# Driver.net
KiCad netlist of a schematic drawn in Altium Designer
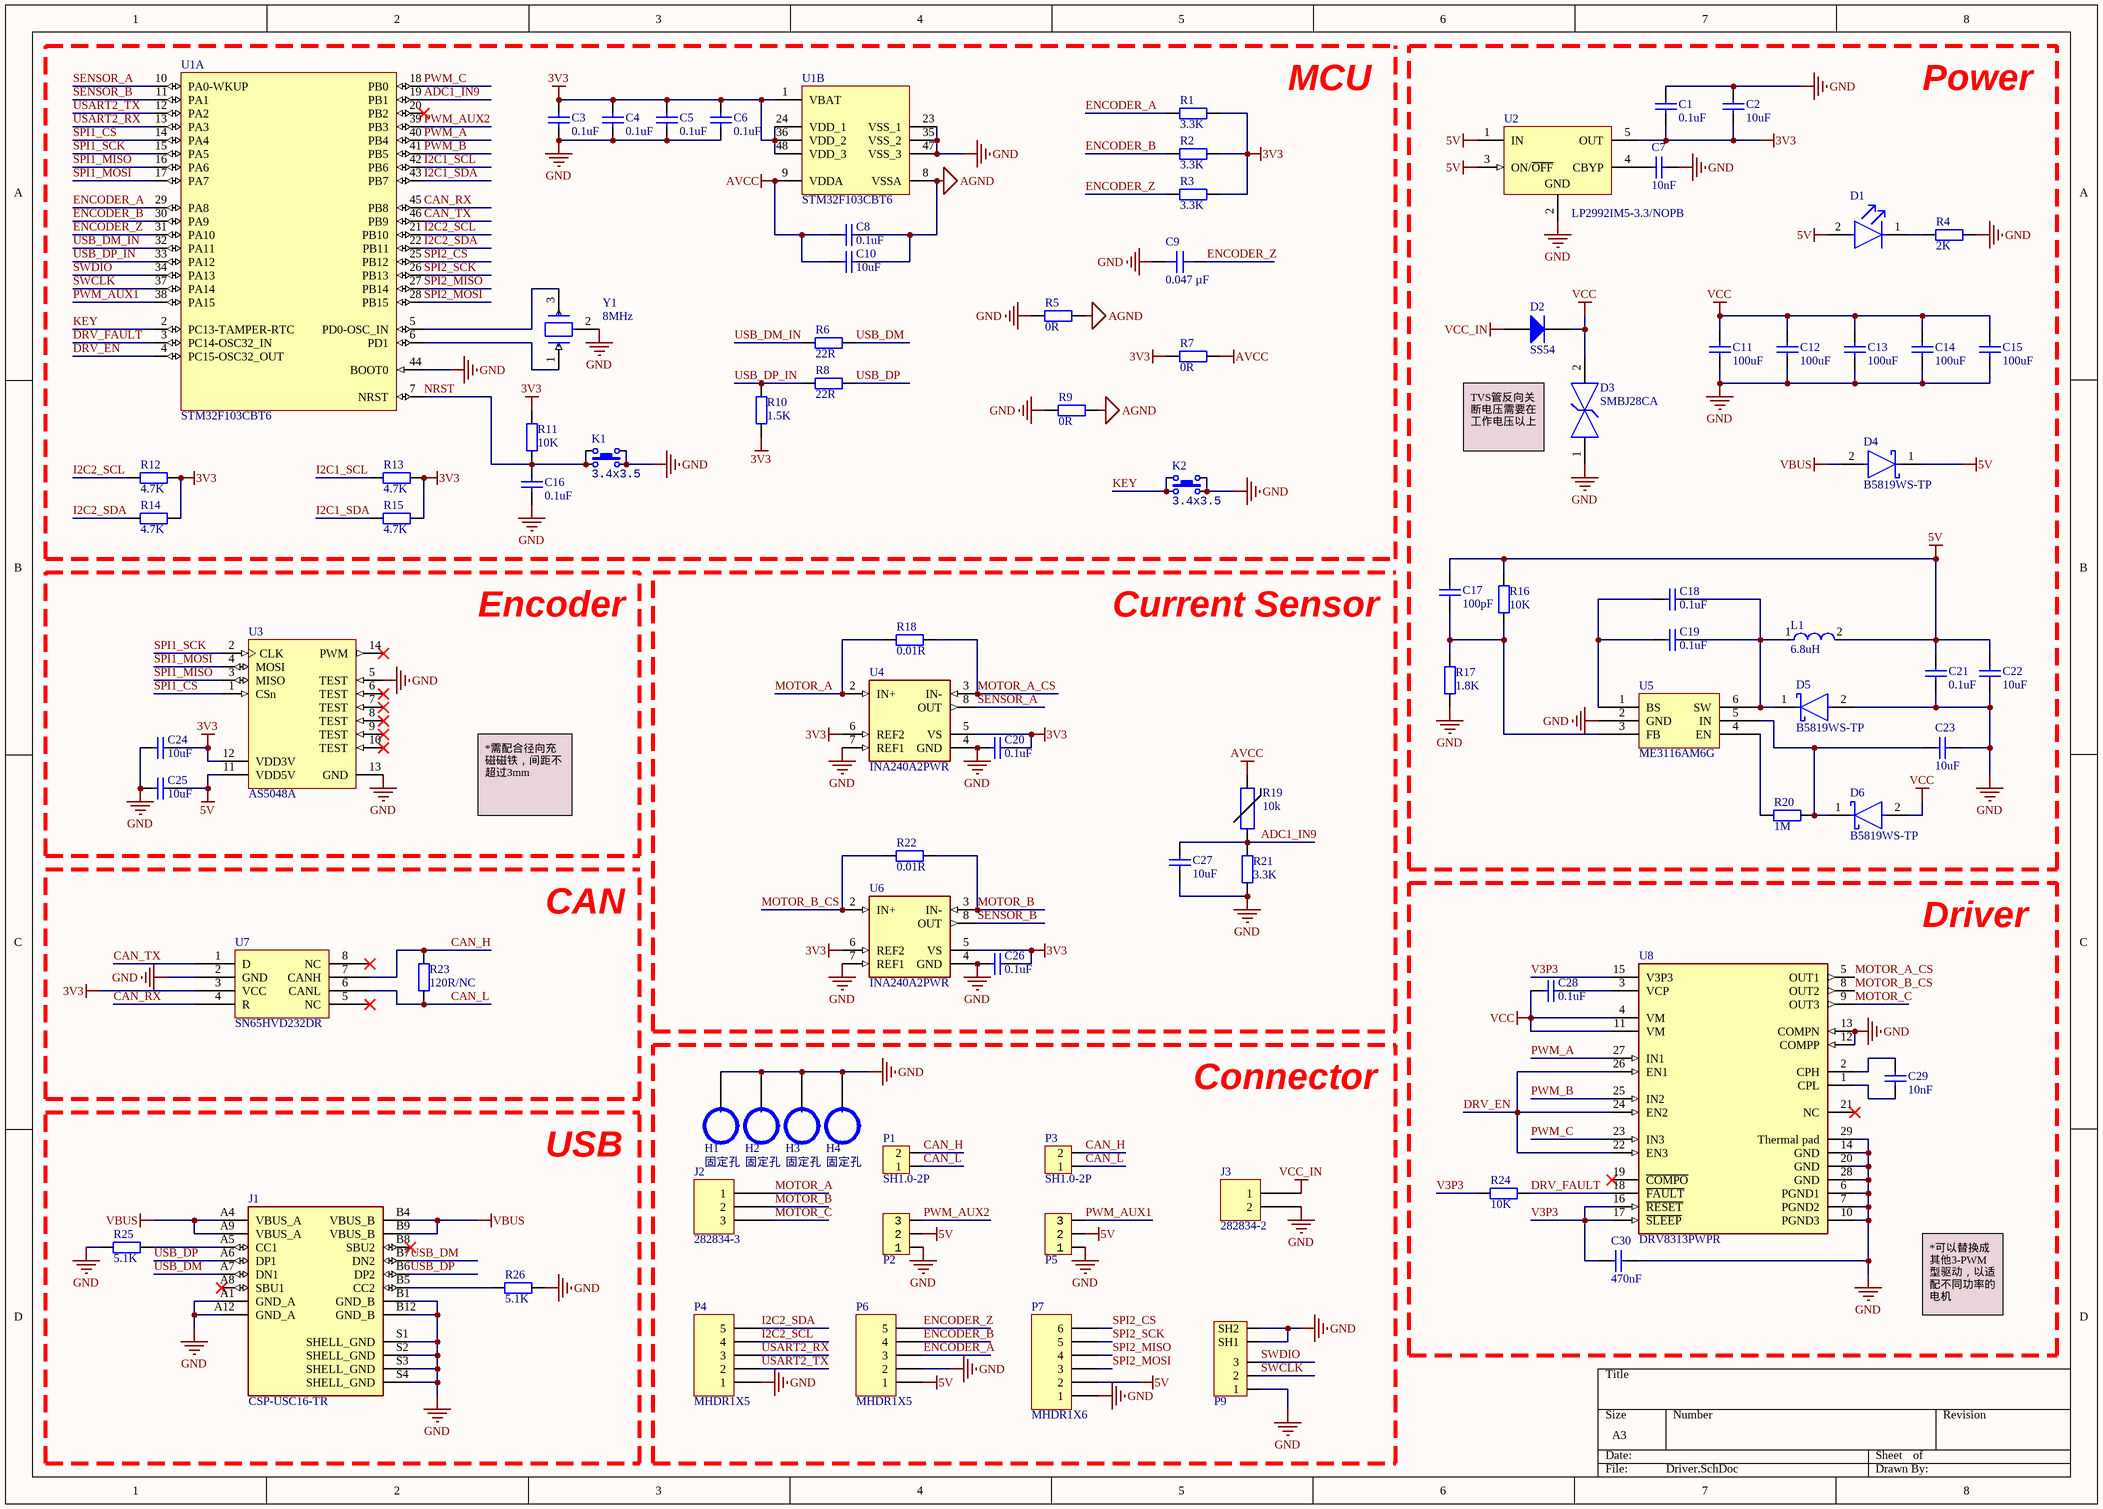
[diagram p0: Driver.SchDoc]

(export (version "E")
  (design (tool "Eeschema 10.0.6"))
  (components
    (comp (ref "C1")
      (value "0.1uF")
      (footprint "0402_C")
      (description "贴片电容")
      (libsource (lib "Miscellaneous Devices LC") (part "0402 100nF (104) 10% 16V"))
    )
    (comp (ref "C2")
      (value "10uF")
      (footprint "0402_C")
      (description "贴片电容")
      (libsource (lib "Miscellaneous Devices LC") (part "0402 100nF (104) 10% 16V"))
    )
    (comp (ref "C3")
      (value "0.1uF")
      (footprint "0402_C")
      (description "贴片电容")
      (libsource (lib "Miscellaneous Devices LC") (part "0402 100nF (104) 10% 16V"))
    )
    (comp (ref "C4")
      (value "0.1uF")
      (footprint "0402_C")
      (description "贴片电容")
      (libsource (lib "Miscellaneous Devices LC") (part "0402 100nF (104) 10% 16V"))
    )
    (comp (ref "C5")
      (value "0.1uF")
      (footprint "0402_C")
      (description "贴片电容")
      (libsource (lib "Miscellaneous Devices LC") (part "0402 100nF (104) 10% 16V"))
    )
    (comp (ref "C6")
      (value "0.1uF")
      (footprint "0402_C")
      (description "贴片电容")
      (libsource (lib "Miscellaneous Devices LC") (part "0402 100nF (104) 10% 16V"))
    )
    (comp (ref "C7")
      (value "10nF")
      (footprint "0402_C")
      (description "贴片电容")
      (libsource (lib "Miscellaneous Devices LC") (part "0402 100nF (104) 10% 16V"))
    )
    (comp (ref "C8")
      (value "0.1uF")
      (footprint "0402_C")
      (description "贴片电容")
      (libsource (lib "Miscellaneous Devices LC") (part "0402 100nF (104) 10% 16V"))
    )
    (comp (ref "C9")
      (value "0.047 µF")
      (footprint "CAP 0402_1005")
      (description "CAP CER 0402 47NF 25V X7R 10%")
      (fields (field (name "PART NUMBER") "C0402C473K3REC7867") (field (name "MANUFACTURER") "KEMET"))
      (libsource (lib "Celestial Altium Library - altium_library") (part "Capacitor"))
    )
    (comp (ref "C10")
      (value "10uF")
      (footprint "0402_C")
      (description "贴片电容")
      (libsource (lib "Miscellaneous Devices LC") (part "0402 100nF (104) 10% 16V"))
    )
    (comp (ref "C11")
      (value "100uF")
      (footprint "CAPC3216X190X55LL30T25")
      (description "Chip Capacitor, 100 uF, +/- 20%, 6.3 V, -55 to 85 degC, 1206 (3216 Metric), RoHS, Tape and Reel")
      (fields (field (name "TOLERANCE") "20%") (field (name "PARTNUMBER") "GRM31CR60J107ME39L"))
      (libsource (lib "Altium Content Vault") (part "CAP-NP-2"))
    )
    (comp (ref "C12")
      (value "100uF")
      (footprint "CAPC3216X190X55LL30T25")
      (description "Chip Capacitor, 100 uF, +/- 20%, 6.3 V, -55 to 85 degC, 1206 (3216 Metric), RoHS, Tape and Reel")
      (fields (field (name "TOLERANCE") "20%") (field (name "PARTNUMBER") "GRM31CR60J107ME39L"))
      (libsource (lib "Altium Content Vault") (part "CAP-NP-2"))
    )
    (comp (ref "C13")
      (value "100uF")
      (footprint "CAPC3216X190X55LL30T25")
      (description "Chip Capacitor, 100 uF, +/- 20%, 6.3 V, -55 to 85 degC, 1206 (3216 Metric), RoHS, Tape and Reel")
      (fields (field (name "TOLERANCE") "20%") (field (name "PARTNUMBER") "GRM31CR60J107ME39L"))
      (libsource (lib "Altium Content Vault") (part "CAP-NP-2"))
    )
    (comp (ref "C14")
      (value "100uF")
      (footprint "CAPC3216X190X55LL30T25")
      (description "Chip Capacitor, 100 uF, +/- 20%, 6.3 V, -55 to 85 degC, 1206 (3216 Metric), RoHS, Tape and Reel")
      (fields (field (name "TOLERANCE") "20%") (field (name "PARTNUMBER") "GRM31CR60J107ME39L"))
      (libsource (lib "Altium Content Vault") (part "CAP-NP-2"))
    )
    (comp (ref "C15")
      (value "100uF")
      (footprint "CAPC3216X190X55LL30T25")
      (description "Chip Capacitor, 100 uF, +/- 20%, 6.3 V, -55 to 85 degC, 1206 (3216 Metric), RoHS, Tape and Reel")
      (fields (field (name "TOLERANCE") "20%") (field (name "PARTNUMBER") "GRM31CR60J107ME39L"))
      (libsource (lib "Altium Content Vault") (part "CAP-NP-2"))
    )
    (comp (ref "C16")
      (value "0.1uF")
      (footprint "0402_C")
      (description "贴片电容")
      (libsource (lib "Miscellaneous Devices LC") (part "0402 100nF (104) 10% 16V"))
    )
    (comp (ref "C17")
      (value "100pF")
      (footprint "0402_C")
      (description "贴片电容")
      (libsource (lib "Miscellaneous Devices LC") (part "0402 100pF (101) 5% 50V"))
    )
    (comp (ref "C18")
      (value "0.1uF")
      (footprint "0402_C")
      (description "贴片电容")
      (libsource (lib "Miscellaneous Devices LC") (part "0402 100nF (104) 10% 16V"))
    )
    (comp (ref "C19")
      (value "0.1uF")
      (footprint "0402_C")
      (description "贴片电容")
      (libsource (lib "Miscellaneous Devices LC") (part "0402 100nF (104) 10% 16V"))
    )
    (comp (ref "C20")
      (value "0.1uF")
      (footprint "0402_C")
      (description "贴片电容")
      (libsource (lib "Miscellaneous Devices LC") (part "0402 100nF (104) 10% 16V"))
    )
    (comp (ref "C21")
      (value "0.1uF")
      (footprint "0402_C")
      (description "贴片电容")
      (libsource (lib "Miscellaneous Devices LC") (part "0402 100nF (104) 10% 16V"))
    )
    (comp (ref "C22")
      (value "10uF")
      (footprint "0402_C")
      (description "贴片电容")
      (libsource (lib "Miscellaneous Devices LC") (part "0402 100nF (104) 10% 16V"))
    )
    (comp (ref "C23")
      (value "10uF")
      (footprint "0402_C")
      (description "贴片电容")
      (libsource (lib "Miscellaneous Devices LC") (part "0402 100nF (104) 10% 16V"))
    )
    (comp (ref "C24")
      (value "10uF")
      (footprint "0402_C")
      (description "贴片电容")
      (libsource (lib "Miscellaneous Devices LC") (part "0402 100nF (104) 10% 16V"))
    )
    (comp (ref "C25")
      (value "10uF")
      (footprint "0402_C")
      (description "贴片电容")
      (libsource (lib "Miscellaneous Devices LC") (part "0402 100nF (104) 10% 16V"))
    )
    (comp (ref "C26")
      (value "0.1uF")
      (footprint "0402_C")
      (description "贴片电容")
      (libsource (lib "Miscellaneous Devices LC") (part "0402 100nF (104) 10% 16V"))
    )
    (comp (ref "C27")
      (value "10uF")
      (footprint "0402_C")
      (description "贴片电容")
      (libsource (lib "Miscellaneous Devices LC") (part "0402 100nF (104) 10% 16V"))
    )
    (comp (ref "C28")
      (value "0.1uF")
      (footprint "0402_C")
      (description "贴片电容")
      (libsource (lib "Miscellaneous Devices LC") (part "0402 100nF (104) 10% 16V"))
    )
    (comp (ref "C29")
      (value "10nF")
      (footprint "0402_C")
      (description "贴片电容")
      (libsource (lib "Miscellaneous Devices LC") (part "0402 10nF (103) 10% 50V"))
    )
    (comp (ref "C30")
      (value "470nF")
      (footprint "0402_C")
      (description "贴片电容")
      (libsource (lib "Miscellaneous Devices LC") (part "0402 470nF (474) 10% 10V"))
    )
    (comp (ref "D1")
      (value "~")
      (footprint "FP-APHHS1005CGCK-MFG")
      (description "LED GREEN CLEAR CHIP SMD")
      (libsource (lib "Altium Content Vault") (part "8706943c75ba83719d021d2fdc84c58"))
    )
    (comp (ref "D2")
      (value "SS54")
      (footprint "SMA(DO-214AC)_S1")
      (description "二极管")
      (libsource (lib "Miscellaneous Devices LC") (part "SMA(DO-214AC) SS54"))
    )
    (comp (ref "D3")
      (value "SMBJ28CA")
      (footprint "FP-SMBJ-CA-MFG")
      (description "TVS DIODE 28V 45.4V DO214AA")
      (fields
        (field (name "MANUFACTURER") "Littelfuse Inc")
        (field (name "OCTOPART") "https://octopart.com/smbj28ca-littelfuse-350757")
      )
      (libsource (lib "Altium Content Vault") (part "89c663e49c8877d2c9d183c2997548d"))
    )
    (comp (ref "D4")
      (value "B5819WS-TP")
      (footprint "FP-SOD-323-IPC_C")
      (description "DIODE SCHOTTKY 40V 1A SOD323")
      (libsource (lib "Altium Content Vault") (part "1d6ec82d83fb6aee721767c19dac4b9"))
    )
    (comp (ref "D5")
      (value "B5819WS-TP")
      (footprint "FP-SOD-323-IPC_C")
      (description "DIODE SCHOTTKY 40V 1A SOD323")
      (libsource (lib "Altium Content Vault") (part "1d6ec82d83fb6aee721767c19dac4b9"))
    )
    (comp (ref "D6")
      (value "B5819WS-TP")
      (footprint "FP-SOD-323-IPC_C")
      (description "DIODE SCHOTTKY 40V 1A SOD323")
      (libsource (lib "Altium Content Vault") (part "1d6ec82d83fb6aee721767c19dac4b9"))
    )
    (comp (ref "H1") (value "固定孔") (footprint "铜柱孔3") (libsource (lib "Rocos-FOC") (part "固定孔")))
    (comp (ref "H2") (value "固定孔") (footprint "铜柱孔3") (libsource (lib "Rocos-FOC") (part "固定孔")))
    (comp (ref "H3") (value "固定孔") (footprint "铜柱孔3") (libsource (lib "Rocos-FOC") (part "固定孔")))
    (comp (ref "H4") (value "固定孔") (footprint "铜柱孔3") (libsource (lib "Rocos-FOC") (part "固定孔")))
    (comp (ref "J1")
      (value "CSP-USC16-TR")
      (footprint "VALCON_CSP-USC16-TR")
      (description "CSP-USC16-TR Valcon USB Type C Surface Mount PCB Socket")
      (fields (field (name "MF") "Valcon"))
      (libsource (lib "Rocos-FOC") (part "CSP-USC16-TR"))
    )
    (comp (ref "J2")
      (value "282834-3")
      (footprint "TE 282834-3")
      (description "TERM BLK 3P SIDE ENT 2.54MM PCB")
      (fields (field (name "MANUFACTURER") "TE Connectivity AMP Connectors") (field (name "VOLTAGE") "150V"))
      (libsource (lib "Rocos-FOC") (part "3 Pin"))
    )
    (comp (ref "J3")
      (value "282834-2")
      (footprint "TE 282834-2")
      (description "TERM BLK 2P SIDE ENT 2.54MM PCB")
      (fields (field (name "MANUFACTURER") "TE Connectivity AMP Connectors") (field (name "VOLTAGE") "150V"))
      (libsource (lib "Rocos-FOC") (part "2 Pin"))
    )
    (comp (ref "K1")
      (value "3.4x3.5")
      (footprint "ButtonTACT_3.5*3.55_90")
      (description "Button")
      (fields (field (name "Comment") "TACT 4P"))
      (libsource (lib "Ctrl-FOC-Lite") (part "ButtonTACT"))
    )
    (comp (ref "K2")
      (value "3.4x3.5")
      (footprint "ButtonTACT_3.5*3.55_90")
      (description "Button")
      (fields (field (name "Comment") "TACT 4P"))
      (libsource (lib "Ctrl-FOC-Lite") (part "ButtonTACT"))
    )
    (comp (ref "L1")
      (value "6.8uH")
      (footprint "FP-LQH2MCN_52-MFG")
      (description "Wire Wound Ferrite Inductor for Power Lines 6.8μH ±20% 1.6Ω 285mA 0806")
      (fields (field (name "TOLERANCE") "20%"))
      (libsource (lib "Altium Content Vault") (part "725321dda6339637d4d059423bc1c3c"))
    )
    (comp (ref "P1")
      (value "SH1.0-2P")
      (footprint "SH1.0-2P")
      (libsource (lib "Rocos-FOC") (part "SH1.0-2P"))
    )
    (comp (ref "P2")
      (value "HDR1x3_2.54")
      (footprint "HDR1X3_2.54_180")
      (description "Header")
      (libsource (lib "Rocos-FOC") (part "HDR1x3_2.54"))
    )
    (comp (ref "P3")
      (value "SH1.0-2P")
      (footprint "SH1.0-2P")
      (libsource (lib "Rocos-FOC") (part "SH1.0-2P"))
    )
    (comp (ref "P4")
      (value "MHDR1X5")
      (footprint "MHDR1X5")
      (description "Header, 5-Pin")
      (fields (field (name "PUBLISHER") "Altium Limited"))
      (libsource (lib "Rocos-FOC") (part "MHDR1X5"))
    )
    (comp (ref "P5")
      (value "HDR1x3_2.54")
      (footprint "HDR1X3_2.54_180")
      (description "Header")
      (libsource (lib "Rocos-FOC") (part "HDR1x3_2.54"))
    )
    (comp (ref "P6")
      (value "MHDR1X5")
      (footprint "MHDR1X5")
      (description "Header, 5-Pin")
      (fields (field (name "PUBLISHER") "Altium Limited"))
      (libsource (lib "Rocos-FOC") (part "MHDR1X5"))
    )
    (comp (ref "P7")
      (value "MHDR1X6")
      (footprint "MHDR1X6")
      (description "Header, 6-Pin")
      (fields (field (name "PUBLISHER") "Altium Limited"))
      (libsource (lib "Rocos-FOC") (part "MHDR1X6"))
    )
    (comp (ref "P9")
      (value "SH1.0-3P")
      (footprint "SH1.0-3P")
      (description "Header")
      (libsource (lib "Rocos-FOC") (part "SH1.0-3P"))
    )
    (comp (ref "R1")
      (value "3.3K")
      (footprint "0402_R")
      (description "贴片电阻")
      (libsource (lib "") (part "0402 3.3KΩ (3301) 1%_1"))
    )
    (comp (ref "R2")
      (value "3.3K")
      (footprint "0402_R")
      (description "贴片电阻")
      (libsource (lib "") (part "0402 3.3KΩ (3301) 1%_1"))
    )
    (comp (ref "R3")
      (value "3.3K")
      (footprint "0402_R")
      (description "贴片电阻")
      (libsource (lib "") (part "0402 3.3KΩ (3301) 1%_1"))
    )
    (comp (ref "R4")
      (value "2K")
      (footprint "0402_R")
      (description "贴片电阻")
      (libsource (lib "Miscellaneous Devices LC") (part "0402 2KΩ (2001) 1%"))
    )
    (comp (ref "R5")
      (value "0R")
      (footprint "0402_R")
      (description "贴片电阻")
      (libsource (lib "Miscellaneous Devices LC") (part "0402 0Ω (0R0) 1%"))
    )
    (comp (ref "R6")
      (value "22R")
      (footprint "0402_R")
      (description "贴片电阻")
      (libsource (lib "") (part "0402 22Ω (22R0) 1%_1"))
    )
    (comp (ref "R7")
      (value "0R")
      (footprint "0402_R")
      (description "贴片电阻")
      (libsource (lib "Miscellaneous Devices LC") (part "0402 0Ω (0R0) 1%"))
    )
    (comp (ref "R8")
      (value "22R")
      (footprint "0402_R")
      (description "贴片电阻")
      (libsource (lib "") (part "0402 22Ω (22R0) 1%_1"))
    )
    (comp (ref "R9")
      (value "0R")
      (footprint "0402_R")
      (description "贴片电阻")
      (libsource (lib "Miscellaneous Devices LC") (part "0402 0Ω (0R0) 1%"))
    )
    (comp (ref "R10")
      (value "1.5K")
      (footprint "0402_R")
      (description "贴片电阻")
      (libsource (lib "Miscellaneous Devices LC") (part "0402 1.5KΩ (1501) 1%"))
    )
    (comp (ref "R11")
      (value "10K")
      (footprint "0402_R")
      (description "贴片电阻")
      (libsource (lib "Miscellaneous Devices LC") (part "0402 10KΩ (1002) 1%"))
    )
    (comp (ref "R12")
      (value "4.7K")
      (footprint "0402_R")
      (description "贴片电阻")
      (libsource (lib "Miscellaneous Devices LC") (part "0402 4.7KΩ (4701) 1%"))
    )
    (comp (ref "R13")
      (value "4.7K")
      (footprint "0402_R")
      (description "贴片电阻")
      (libsource (lib "Miscellaneous Devices LC") (part "0402 4.7KΩ (4701) 1%"))
    )
    (comp (ref "R14")
      (value "4.7K")
      (footprint "0402_R")
      (description "贴片电阻")
      (libsource (lib "Miscellaneous Devices LC") (part "0402 4.7KΩ (4701) 1%"))
    )
    (comp (ref "R15")
      (value "4.7K")
      (footprint "0402_R")
      (description "贴片电阻")
      (libsource (lib "Miscellaneous Devices LC") (part "0402 4.7KΩ (4701) 1%"))
    )
    (comp (ref "R16")
      (value "10K")
      (footprint "0402_R")
      (description "贴片电阻")
      (libsource (lib "") (part "0402 1.2KΩ (1201) 1%_1"))
    )
    (comp (ref "R17")
      (value "1.8K")
      (footprint "0402_R")
      (description "贴片电阻")
      (libsource (lib "") (part "0402 1.2KΩ (1201) 1%_1"))
    )
    (comp (ref "R18")
      (value "0.01R")
      (footprint "0402_R")
      (description "贴片电阻")
      (libsource (lib "Miscellaneous Devices LC") (part "0402 22Ω (22R0) 1%"))
    )
    (comp (ref "R19")
      (value "10k")
      (footprint "RES_0402")
      (description "THERMISTOR 10K OHM NTC 0402 SMD")
      (fields (field (name "Comment") "NCP15XH103F03RC"))
      (libsource (lib "Ctrl-FOC-Lite") (part "NCP15XH103F03RC"))
    )
    (comp (ref "R20")
      (value "1M")
      (footprint "0402_R")
      (description "贴片电阻")
      (libsource (lib "") (part "0402 2KΩ (2001) 1%_1"))
    )
    (comp (ref "R21")
      (value "3.3K")
      (footprint "0402_R")
      (description "贴片电阻")
      (libsource (lib "Miscellaneous Devices LC") (part "0402 3.3KΩ (3301) 1%"))
    )
    (comp (ref "R22")
      (value "0.01R")
      (footprint "0402_R")
      (description "贴片电阻")
      (libsource (lib "Miscellaneous Devices LC") (part "0402 22Ω (22R0) 1%"))
    )
    (comp (ref "R23")
      (value "120R/NC")
      (footprint "0402_R")
      (description "贴片电阻")
      (libsource (lib "Miscellaneous Devices LC") (part "0402 120Ω (1200) 1%"))
    )
    (comp (ref "R24")
      (value "10K")
      (footprint "0402_R")
      (description "贴片电阻")
      (libsource (lib "Miscellaneous Devices LC") (part "0402 1.2KΩ (1201) 1%"))
    )
    (comp (ref "R25")
      (value "5.1K")
      (footprint "0402_R")
      (description "贴片电阻")
      (libsource (lib "Miscellaneous Devices LC") (part "0402 1.2KΩ (1201) 1%"))
    )
    (comp (ref "R26")
      (value "5.1K")
      (footprint "0402_R")
      (description "贴片电阻")
      (libsource (lib "Miscellaneous Devices LC") (part "0402 1.2KΩ (1201) 1%"))
    )
    (comp (ref "U1")
      (value "STM32F103CBT6")
      (footprint "LQFP-48_7x7x05P")
      (description "ARM")
      (libsource (lib "Rocos-FOC") (part "STM32F103CBT6"))
    )
    (comp (ref "U2")
      (value "LP2992IM5-3.3/NOPB")
      (footprint "DBV0005A_L")
      (description "Micropower 250 mA Low-Noise Ultra Low-Dropout Regulator, 5-pin SOT-23, Pb-Free")
      (fields (field (name "MANUFACTURER") "Texas Instruments"))
      (libsource (lib "Altium Content Vault") (part "PM-REG-LP2985-SOT5"))
    )
    (comp (ref "U3")
      (value "AS5048A")
      (footprint "TSSOP-14")
      (description "14 位旋转式位置传感器")
      (libsource (lib "Rocos-FOC") (part "AS5048A"))
    )
    (comp (ref "U4")
      (value "INA240A2PWR")
      (footprint "SOP65 P640X120-8N")
      (fields (field (name "MF") "Texas Instruments"))
      (libsource (lib "Rocos-FOC") (part "INA240A2PWR"))
    )
    (comp (ref "U5")
      (value "ME3116AM6G")
      (footprint "SOT-23-6")
      (description "DC/DC降压型稳压器")
      (libsource (lib "Rocos-FOC") (part "ME3116AM6G"))
    )
    (comp (ref "U6")
      (value "INA240A2PWR")
      (footprint "SOP65 P640X120-8N")
      (fields (field (name "MF") "Texas Instruments"))
      (libsource (lib "Rocos-FOC") (part "INA240A2PWR"))
    )
    (comp (ref "U7")
      (value "SN65HVD232D")
      (footprint "SO-8")
      (fields
        (field (name "MANUFACTURER") "Texas Instruments")
        (field (name "MANUFACTURER PART NUMBER") "SN65HVD232DR")
      )
      (libsource (lib "Rocos-FOC") (part "SN65HVD232D"))
    )
    (comp (ref "U8")
      (value "DRV8313PWPR")
      (footprint "FP-PWP0028C-IPC_B")
      (description "IC MOTOR DRIVER 8V-60V 28HTSSOP")
      (libsource (lib "Altium Content Vault") (part "6c5e8d1d79df7918d4eb9ae5de6b4b8"))
    )
    (comp (ref "Y1")
      (value "8MHz")
      (footprint "FP-CSTNE8M00GH5C000R0-MFG")
      (description "CERAMIC RES 8.0000MHZ 33PF SMD")
      (libsource (lib "Altium Content Vault") (part "7d37667f5012bb31280c8009ddd0b1c"))
    )
  )
  (nets
    (net (code "1") (name "/ADC1_IN9") (class "Default")
      (node (ref "C27") (pin "1") (pinfunction "1_1") (pintype "passive"))
      (node (ref "R19") (pin "1") (pinfunction "0_1") (pintype "passive"))
      (node (ref "R21") (pin "2") (pinfunction "2_2") (pintype "passive"))
      (node (ref "U1") (pin "19") (pinfunction "PB1_19") (pintype "bidirectional"))
    )
    (net (code "2") (name "/CAN_H") (class "Default")
      (node (ref "P1") (pin "2") (pinfunction "2_2") (pintype "passive"))
      (node (ref "P3") (pin "2") (pinfunction "2_2") (pintype "passive"))
      (node (ref "R23") (pin "2") (pinfunction "2_2") (pintype "passive"))
      (node (ref "U7") (pin "7") (pinfunction "CANH_7") (pintype "passive"))
    )
    (net (code "3") (name "/CAN_L") (class "Default")
      (node (ref "P1") (pin "1") (pinfunction "1_1") (pintype "passive"))
      (node (ref "P3") (pin "1") (pinfunction "1_1") (pintype "passive"))
      (node (ref "R23") (pin "1") (pinfunction "1_1") (pintype "passive"))
      (node (ref "U7") (pin "6") (pinfunction "CANL_6") (pintype "passive"))
    )
    (net (code "4") (name "/CAN_RX") (class "Default")
      (node (ref "U1") (pin "45") (pinfunction "PB8_45") (pintype "bidirectional"))
      (node (ref "U7") (pin "4") (pinfunction "R_4") (pintype "passive"))
    )
    (net (code "5") (name "/CAN_TX") (class "Default")
      (node (ref "U1") (pin "46") (pinfunction "PB9_46") (pintype "bidirectional"))
      (node (ref "U7") (pin "1") (pinfunction "D_1") (pintype "passive"))
    )
    (net (code "6") (name "/DRV_EN") (class "Default")
      (node (ref "U1") (pin "4") (pinfunction "PC15-OSC32_OUT_4") (pintype "bidirectional"))
      (node (ref "U8") (pin "22") (pinfunction "EN3_22") (pintype "input"))
      (node (ref "U8") (pin "24") (pinfunction "EN2_24") (pintype "input"))
      (node (ref "U8") (pin "26") (pinfunction "EN1_26") (pintype "input"))
    )
    (net (code "7") (name "/DRV_FAULT") (class "Default")
      (node (ref "R24") (pin "1") (pinfunction "1_1") (pintype "passive"))
      (node (ref "U1") (pin "3") (pinfunction "PC14-OSC32_IN_3") (pintype "bidirectional"))
      (node (ref "U8") (pin "18") (pinfunction "~{FAULT}_18") (pintype "open_collector"))
    )
    (net (code "8") (name "/ENCODER_A") (class "Default")
      (node (ref "P6") (pin "3") (pinfunction "3_3") (pintype "passive"))
      (node (ref "R1") (pin "1") (pinfunction "1_1") (pintype "passive"))
      (node (ref "U1") (pin "29") (pinfunction "PA8_29") (pintype "bidirectional"))
    )
    (net (code "9") (name "/ENCODER_B") (class "Default")
      (node (ref "P6") (pin "4") (pinfunction "4_4") (pintype "passive"))
      (node (ref "R2") (pin "1") (pinfunction "1_1") (pintype "passive"))
      (node (ref "U1") (pin "30") (pinfunction "PA9_30") (pintype "bidirectional"))
    )
    (net (code "10") (name "/ENCODER_Z") (class "Default")
      (node (ref "C9") (pin "2") (pinfunction "2_2") (pintype "passive"))
      (node (ref "P6") (pin "5") (pinfunction "5_5") (pintype "passive"))
      (node (ref "R3") (pin "1") (pinfunction "1_1") (pintype "passive"))
      (node (ref "U1") (pin "31") (pinfunction "PA10_31") (pintype "bidirectional"))
    )
    (net (code "11") (name "/I2C1_SCL") (class "Default")
      (node (ref "R13") (pin "1") (pinfunction "1_1") (pintype "passive"))
      (node (ref "U1") (pin "42") (pinfunction "PB6_42") (pintype "bidirectional"))
    )
    (net (code "12") (name "/I2C1_SDA") (class "Default")
      (node (ref "R15") (pin "1") (pinfunction "1_1") (pintype "passive"))
      (node (ref "U1") (pin "43") (pinfunction "PB7_43") (pintype "bidirectional"))
    )
    (net (code "13") (name "/I2C2_SCL") (class "Default")
      (node (ref "P4") (pin "4") (pinfunction "4_4") (pintype "passive"))
      (node (ref "R12") (pin "1") (pinfunction "1_1") (pintype "passive"))
      (node (ref "U1") (pin "21") (pinfunction "PB10_21") (pintype "bidirectional"))
    )
    (net (code "14") (name "/I2C2_SDA") (class "Default")
      (node (ref "P4") (pin "5") (pinfunction "5_5") (pintype "passive"))
      (node (ref "R14") (pin "1") (pinfunction "1_1") (pintype "passive"))
      (node (ref "U1") (pin "22") (pinfunction "PB11_22") (pintype "bidirectional"))
    )
    (net (code "15") (name "/KEY") (class "Default")
      (node (ref "K2") (pin "1") (pinfunction "1_1") (pintype "passive"))
      (node (ref "K2") (pin "3") (pinfunction "3_3") (pintype "passive"))
      (node (ref "U1") (pin "2") (pinfunction "PC13-TAMPER-RTC_2") (pintype "bidirectional"))
    )
    (net (code "16") (name "/MOTOR_A") (class "Default")
      (node (ref "J2") (pin "1") (pinfunction "1_1") (pintype "passive"))
      (node (ref "R18") (pin "2") (pinfunction "2_2") (pintype "passive"))
      (node (ref "U4") (pin "2") (pinfunction "IN+_2") (pintype "input"))
    )
    (net (code "17") (name "/MOTOR_A_CS") (class "Default")
      (node (ref "R18") (pin "1") (pinfunction "1_1") (pintype "passive"))
      (node (ref "U4") (pin "3") (pinfunction "IN-_3") (pintype "input"))
      (node (ref "U8") (pin "5") (pinfunction "OUT1_5") (pintype "output"))
    )
    (net (code "18") (name "/MOTOR_B") (class "Default")
      (node (ref "J2") (pin "2") (pinfunction "2_2") (pintype "passive"))
      (node (ref "R22") (pin "1") (pinfunction "1_1") (pintype "passive"))
      (node (ref "U6") (pin "3") (pinfunction "IN-_3") (pintype "input"))
    )
    (net (code "19") (name "/MOTOR_B_CS") (class "Default")
      (node (ref "R22") (pin "2") (pinfunction "2_2") (pintype "passive"))
      (node (ref "U6") (pin "2") (pinfunction "IN+_2") (pintype "input"))
      (node (ref "U8") (pin "8") (pinfunction "OUT2_8") (pintype "output"))
    )
    (net (code "20") (name "/MOTOR_C") (class "Default")
      (node (ref "J2") (pin "3") (pinfunction "3_3") (pintype "passive"))
      (node (ref "U8") (pin "9") (pinfunction "OUT3_9") (pintype "output"))
    )
    (net (code "21") (name "/NRST") (class "Default")
      (node (ref "C16") (pin "1") (pinfunction "1_1") (pintype "passive"))
      (node (ref "K1") (pin "1") (pinfunction "1_1") (pintype "passive"))
      (node (ref "K1") (pin "3") (pinfunction "3_3") (pintype "passive"))
      (node (ref "R11") (pin "1") (pinfunction "1_1") (pintype "passive"))
      (node (ref "U1") (pin "7") (pinfunction "NRST_7") (pintype "bidirectional"))
    )
    (net (code "22") (name "/PWM_A") (class "Default")
      (node (ref "U1") (pin "40") (pinfunction "PB4_40") (pintype "bidirectional"))
      (node (ref "U8") (pin "27") (pinfunction "IN1_27") (pintype "input"))
    )
    (net (code "23") (name "/PWM_AUX1") (class "Default")
      (node (ref "P5") (pin "3") (pinfunction "3_3") (pintype "passive"))
      (node (ref "U1") (pin "38") (pinfunction "PA15_38") (pintype "bidirectional"))
    )
    (net (code "24") (name "/PWM_AUX2") (class "Default")
      (node (ref "P2") (pin "3") (pinfunction "3_3") (pintype "passive"))
      (node (ref "U1") (pin "39") (pinfunction "PB3_39") (pintype "bidirectional"))
    )
    (net (code "25") (name "/PWM_B") (class "Default")
      (node (ref "U1") (pin "41") (pinfunction "PB5_41") (pintype "bidirectional"))
      (node (ref "U8") (pin "25") (pinfunction "IN2_25") (pintype "input"))
    )
    (net (code "26") (name "/PWM_C") (class "Default")
      (node (ref "U1") (pin "18") (pinfunction "PB0_18") (pintype "bidirectional"))
      (node (ref "U8") (pin "23") (pinfunction "IN3_23") (pintype "input"))
    )
    (net (code "27") (name "/SENSOR_A") (class "Default")
      (node (ref "U1") (pin "10") (pinfunction "PA0-WKUP_10") (pintype "bidirectional"))
      (node (ref "U4") (pin "8") (pinfunction "OUT_8") (pintype "output"))
    )
    (net (code "28") (name "/SENSOR_B") (class "Default")
      (node (ref "U1") (pin "11") (pinfunction "PA1_11") (pintype "bidirectional"))
      (node (ref "U6") (pin "8") (pinfunction "OUT_8") (pintype "output"))
    )
    (net (code "29") (name "/SPI1_CS") (class "Default")
      (node (ref "U1") (pin "14") (pinfunction "PA4_14") (pintype "bidirectional"))
      (node (ref "U3") (pin "1") (pinfunction "CSn_1") (pintype "input"))
    )
    (net (code "30") (name "/SPI1_MISO") (class "Default")
      (node (ref "U1") (pin "16") (pinfunction "PA6_16") (pintype "bidirectional"))
      (node (ref "U3") (pin "3") (pinfunction "MISO_3") (pintype "bidirectional"))
    )
    (net (code "31") (name "/SPI1_MOSI") (class "Default")
      (node (ref "U1") (pin "17") (pinfunction "PA7_17") (pintype "bidirectional"))
      (node (ref "U3") (pin "4") (pinfunction "MOSI_4") (pintype "bidirectional"))
    )
    (net (code "32") (name "/SPI1_SCK") (class "Default")
      (node (ref "U1") (pin "15") (pinfunction "PA5_15") (pintype "bidirectional"))
      (node (ref "U3") (pin "2") (pinfunction "CLK_2") (pintype "input"))
    )
    (net (code "33") (name "/SPI2_CS") (class "Default")
      (node (ref "P7") (pin "6") (pinfunction "6_6") (pintype "passive"))
      (node (ref "U1") (pin "25") (pinfunction "PB12_25") (pintype "bidirectional"))
    )
    (net (code "34") (name "/SPI2_MISO") (class "Default")
      (node (ref "P7") (pin "4") (pinfunction "4_4") (pintype "passive"))
      (node (ref "U1") (pin "27") (pinfunction "PB14_27") (pintype "bidirectional"))
    )
    (net (code "35") (name "/SPI2_MOSI") (class "Default")
      (node (ref "P7") (pin "3") (pinfunction "3_3") (pintype "passive"))
      (node (ref "U1") (pin "28") (pinfunction "PB15_28") (pintype "bidirectional"))
    )
    (net (code "36") (name "/SPI2_SCK") (class "Default")
      (node (ref "P7") (pin "5") (pinfunction "5_5") (pintype "passive"))
      (node (ref "U1") (pin "26") (pinfunction "PB13_26") (pintype "bidirectional"))
    )
    (net (code "37") (name "/SWCLK") (class "Default")
      (node (ref "P9") (pin "2") (pinfunction "2_2") (pintype "passive"))
      (node (ref "U1") (pin "37") (pinfunction "PA14_37") (pintype "bidirectional"))
    )
    (net (code "38") (name "/SWDIO") (class "Default")
      (node (ref "P9") (pin "3") (pinfunction "3_3") (pintype "passive"))
      (node (ref "U1") (pin "34") (pinfunction "PA13_34") (pintype "bidirectional"))
    )
    (net (code "39") (name "/USART2_RX") (class "Default")
      (node (ref "P4") (pin "3") (pinfunction "3_3") (pintype "passive"))
      (node (ref "U1") (pin "13") (pinfunction "PA3_13") (pintype "bidirectional"))
    )
    (net (code "40") (name "/USART2_TX") (class "Default")
      (node (ref "P4") (pin "2") (pinfunction "2_2") (pintype "passive"))
      (node (ref "U1") (pin "12") (pinfunction "PA2_12") (pintype "bidirectional"))
    )
    (net (code "41") (name "/USB_DM") (class "Default")
      (node (ref "J1") (pin "A7") (pinfunction "DN1_A7") (pintype "bidirectional"))
      (node (ref "J1") (pin "B7") (pinfunction "DN2_B7") (pintype "bidirectional"))
      (node (ref "R6") (pin "2") (pinfunction "2_2") (pintype "passive"))
    )
    (net (code "42") (name "/USB_DM_IN") (class "Default")
      (node (ref "R6") (pin "1") (pinfunction "1_1") (pintype "passive"))
      (node (ref "U1") (pin "32") (pinfunction "PA11_32") (pintype "bidirectional"))
    )
    (net (code "43") (name "/USB_DP") (class "Default")
      (node (ref "J1") (pin "A6") (pinfunction "DP1_A6") (pintype "bidirectional"))
      (node (ref "J1") (pin "B6") (pinfunction "DP2_B6") (pintype "bidirectional"))
      (node (ref "R8") (pin "2") (pinfunction "2_2") (pintype "passive"))
    )
    (net (code "44") (name "/USB_DP_IN") (class "Default")
      (node (ref "R10") (pin "2") (pinfunction "2_2") (pintype "passive"))
      (node (ref "R8") (pin "1") (pinfunction "1_1") (pintype "passive"))
      (node (ref "U1") (pin "33") (pinfunction "PA12_33") (pintype "bidirectional"))
    )
    (net (code "45") (name "/V3P3") (class "Default")
      (node (ref "C30") (pin "1") (pinfunction "1_1") (pintype "passive"))
      (node (ref "R24") (pin "2") (pinfunction "2_2") (pintype "passive"))
      (node (ref "U8") (pin "15") (pinfunction "V3P3_15") (pintype "power_in"))
      (node (ref "U8") (pin "16") (pinfunction "~{RESET}_16") (pintype "input"))
      (node (ref "U8") (pin "17") (pinfunction "~{SLEEP}_17") (pintype "input"))
    )
    (net (code "46") (name "3V3") (class "Default")
      (node (ref "C1") (pin "1") (pinfunction "1_1") (pintype "passive"))
      (node (ref "C2") (pin "1") (pinfunction "1_1") (pintype "passive"))
      (node (ref "C20") (pin "1") (pinfunction "1_1") (pintype "passive"))
      (node (ref "C24") (pin "1") (pinfunction "1_1") (pintype "passive"))
      (node (ref "C26") (pin "1") (pinfunction "1_1") (pintype "passive"))
      (node (ref "C3") (pin "1") (pinfunction "1_1") (pintype "passive"))
      (node (ref "C4") (pin "1") (pinfunction "1_1") (pintype "passive"))
      (node (ref "C5") (pin "1") (pinfunction "1_1") (pintype "passive"))
      (node (ref "C6") (pin "1") (pinfunction "1_1") (pintype "passive"))
      (node (ref "R1") (pin "2") (pinfunction "2_2") (pintype "passive"))
      (node (ref "R10") (pin "1") (pinfunction "1_1") (pintype "passive"))
      (node (ref "R11") (pin "2") (pinfunction "2_2") (pintype "passive"))
      (node (ref "R12") (pin "2") (pinfunction "2_2") (pintype "passive"))
      (node (ref "R13") (pin "2") (pinfunction "2_2") (pintype "passive"))
      (node (ref "R14") (pin "2") (pinfunction "2_2") (pintype "passive"))
      (node (ref "R15") (pin "2") (pinfunction "2_2") (pintype "passive"))
      (node (ref "R2") (pin "2") (pinfunction "2_2") (pintype "passive"))
      (node (ref "R3") (pin "2") (pinfunction "2_2") (pintype "passive"))
      (node (ref "R7") (pin "1") (pinfunction "1_1") (pintype "passive"))
      (node (ref "U1") (pin "1") (pinfunction "VBAT_1") (pintype "power_in"))
      (node (ref "U1") (pin "24") (pinfunction "VDD_1_24") (pintype "power_in"))
      (node (ref "U1") (pin "36") (pinfunction "VDD_2_36") (pintype "power_in"))
      (node (ref "U1") (pin "48") (pinfunction "VDD_3_48") (pintype "power_in"))
      (node (ref "U2") (pin "5") (pinfunction "OUT_5") (pintype "power_in"))
      (node (ref "U3") (pin "12") (pinfunction "VDD3V_12") (pintype "power_in"))
      (node (ref "U4") (pin "5") (pinfunction "VS_5") (pintype "power_in"))
      (node (ref "U4") (pin "6") (pinfunction "REF2_6") (pintype "input"))
      (node (ref "U6") (pin "5") (pinfunction "VS_5") (pintype "power_in"))
      (node (ref "U6") (pin "6") (pinfunction "REF2_6") (pintype "input"))
      (node (ref "U7") (pin "3") (pinfunction "VCC_3") (pintype "passive"))
    )
    (net (code "47") (name "5V") (class "Default")
      (node (ref "C17") (pin "2") (pinfunction "2_2") (pintype "passive"))
      (node (ref "C21") (pin "1") (pinfunction "1_1") (pintype "passive"))
      (node (ref "C22") (pin "2") (pinfunction "2_2") (pintype "passive"))
      (node (ref "C25") (pin "1") (pinfunction "1_1") (pintype "passive"))
      (node (ref "D1") (pin "2") (pinfunction "A_2") (pintype "passive"))
      (node (ref "D4") (pin "1") (pinfunction "C_1") (pintype "passive"))
      (node (ref "L1") (pin "2") (pinfunction "2_2") (pintype "passive"))
      (node (ref "P2") (pin "2") (pinfunction "2_2") (pintype "passive"))
      (node (ref "P5") (pin "2") (pinfunction "2_2") (pintype "passive"))
      (node (ref "P6") (pin "1") (pinfunction "1_1") (pintype "passive"))
      (node (ref "P7") (pin "2") (pinfunction "2_2") (pintype "passive"))
      (node (ref "R16") (pin "2") (pinfunction "2_2") (pintype "passive"))
      (node (ref "U2") (pin "1") (pinfunction "IN_1") (pintype "power_in"))
      (node (ref "U2") (pin "3") (pinfunction "ON/~{OFF}_3") (pintype "input"))
      (node (ref "U3") (pin "11") (pinfunction "VDD5V_11") (pintype "power_in"))
    )
    (net (code "48") (name "AGND") (class "Default")
      (node (ref "C10") (pin "1") (pinfunction "1_1") (pintype "passive"))
      (node (ref "C8") (pin "1") (pinfunction "1_1") (pintype "passive"))
      (node (ref "R5") (pin "2") (pinfunction "2_2") (pintype "passive"))
      (node (ref "R9") (pin "2") (pinfunction "2_2") (pintype "passive"))
      (node (ref "U1") (pin "8") (pinfunction "VSSA_8") (pintype "power_in"))
    )
    (net (code "49") (name "AVCC") (class "Default")
      (node (ref "C10") (pin "2") (pinfunction "2_2") (pintype "passive"))
      (node (ref "C8") (pin "2") (pinfunction "2_2") (pintype "passive"))
      (node (ref "R19") (pin "2") (pinfunction "0_2") (pintype "passive"))
      (node (ref "R7") (pin "2") (pinfunction "2_2") (pintype "passive"))
      (node (ref "U1") (pin "9") (pinfunction "VDDA_9") (pintype "power_in"))
    )
    (net (code "50") (name "GND") (class "Default")
      (node (ref "C1") (pin "2") (pinfunction "2_2") (pintype "passive"))
      (node (ref "C11") (pin "1") (pinfunction "1_1") (pintype "passive"))
      (node (ref "C12") (pin "1") (pinfunction "1_1") (pintype "passive"))
      (node (ref "C13") (pin "1") (pinfunction "1_1") (pintype "passive"))
      (node (ref "C14") (pin "1") (pinfunction "1_1") (pintype "passive"))
      (node (ref "C15") (pin "1") (pinfunction "1_1") (pintype "passive"))
      (node (ref "C16") (pin "2") (pinfunction "2_2") (pintype "passive"))
      (node (ref "C2") (pin "2") (pinfunction "2_2") (pintype "passive"))
      (node (ref "C20") (pin "2") (pinfunction "2_2") (pintype "passive"))
      (node (ref "C21") (pin "2") (pinfunction "2_2") (pintype "passive"))
      (node (ref "C22") (pin "1") (pinfunction "1_1") (pintype "passive"))
      (node (ref "C23") (pin "1") (pinfunction "1_1") (pintype "passive"))
      (node (ref "C24") (pin "2") (pinfunction "2_2") (pintype "passive"))
      (node (ref "C25") (pin "2") (pinfunction "2_2") (pintype "passive"))
      (node (ref "C26") (pin "2") (pinfunction "2_2") (pintype "passive"))
      (node (ref "C27") (pin "2") (pinfunction "2_2") (pintype "passive"))
      (node (ref "C3") (pin "2") (pinfunction "2_2") (pintype "passive"))
      (node (ref "C30") (pin "2") (pinfunction "2_2") (pintype "passive"))
      (node (ref "C4") (pin "2") (pinfunction "2_2") (pintype "passive"))
      (node (ref "C5") (pin "2") (pinfunction "2_2") (pintype "passive"))
      (node (ref "C6") (pin "2") (pinfunction "2_2") (pintype "passive"))
      (node (ref "C7") (pin "1") (pinfunction "1_1") (pintype "passive"))
      (node (ref "C9") (pin "1") (pinfunction "1_1") (pintype "passive"))
      (node (ref "D3") (pin "1") (pinfunction "1_1") (pintype "passive"))
      (node (ref "D5") (pin "2") (pinfunction "A_2") (pintype "passive"))
      (node (ref "H1") (pin "11") (pinfunction "11_11") (pintype "passive"))
      (node (ref "H2") (pin "11") (pinfunction "11_11") (pintype "passive"))
      (node (ref "H3") (pin "11") (pinfunction "11_11") (pintype "passive"))
      (node (ref "H4") (pin "11") (pinfunction "11_11") (pintype "passive"))
      (node (ref "J1") (pin "A1") (pinfunction "GND_A_A1") (pintype "power_in"))
      (node (ref "J1") (pin "A12") (pinfunction "GND_A_A12") (pintype "power_in"))
      (node (ref "J1") (pin "B1") (pinfunction "GND_B_B1") (pintype "power_in"))
      (node (ref "J1") (pin "B12") (pinfunction "GND_B_B12") (pintype "power_in"))
      (node (ref "J1") (pin "S1") (pinfunction "SHELL_GND_S1") (pintype "power_in"))
      (node (ref "J1") (pin "S2") (pinfunction "SHELL_GND_S2") (pintype "power_in"))
      (node (ref "J1") (pin "S3") (pinfunction "SHELL_GND_S3") (pintype "power_in"))
      (node (ref "J1") (pin "S4") (pinfunction "SHELL_GND_S4") (pintype "power_in"))
      (node (ref "J3") (pin "2") (pinfunction "2_2") (pintype "passive"))
      (node (ref "K1") (pin "2") (pinfunction "2_2") (pintype "passive"))
      (node (ref "K1") (pin "4") (pinfunction "4_4") (pintype "passive"))
      (node (ref "K2") (pin "2") (pinfunction "2_2") (pintype "passive"))
      (node (ref "K2") (pin "4") (pinfunction "4_4") (pintype "passive"))
      (node (ref "P2") (pin "1") (pinfunction "1_1") (pintype "passive"))
      (node (ref "P4") (pin "1") (pinfunction "1_1") (pintype "passive"))
      (node (ref "P5") (pin "1") (pinfunction "1_1") (pintype "passive"))
      (node (ref "P6") (pin "2") (pinfunction "2_2") (pintype "passive"))
      (node (ref "P7") (pin "1") (pinfunction "1_1") (pintype "passive"))
      (node (ref "P9") (pin "1") (pinfunction "1_1") (pintype "passive"))
      (node (ref "P9") (pin "SH1") (pinfunction "SH1_SH1") (pintype "passive"))
      (node (ref "P9") (pin "SH2") (pinfunction "SH2_SH2") (pintype "passive"))
      (node (ref "R17") (pin "1") (pinfunction "1_1") (pintype "passive"))
      (node (ref "R21") (pin "1") (pinfunction "1_1") (pintype "passive"))
      (node (ref "R25") (pin "2") (pinfunction "2_2") (pintype "passive"))
      (node (ref "R26") (pin "1") (pinfunction "1_1") (pintype "passive"))
      (node (ref "R4") (pin "2") (pinfunction "2_2") (pintype "passive"))
      (node (ref "R5") (pin "1") (pinfunction "1_1") (pintype "passive"))
      (node (ref "R9") (pin "1") (pinfunction "1_1") (pintype "passive"))
      (node (ref "U1") (pin "23") (pinfunction "VSS_1_23") (pintype "power_in"))
      (node (ref "U1") (pin "35") (pinfunction "VSS_2_35") (pintype "power_in"))
      (node (ref "U1") (pin "44") (pinfunction "BOOT0_44") (pintype "input"))
      (node (ref "U1") (pin "47") (pinfunction "VSS_3_47") (pintype "power_in"))
      (node (ref "U2") (pin "2") (pinfunction "GND_2") (pintype "power_in"))
      (node (ref "U3") (pin "13") (pinfunction "GND_13") (pintype "power_in"))
      (node (ref "U3") (pin "5") (pinfunction "TEST_5") (pintype "input"))
      (node (ref "U4") (pin "4") (pinfunction "GND_4") (pintype "power_in"))
      (node (ref "U4") (pin "7") (pinfunction "REF1_7") (pintype "input"))
      (node (ref "U5") (pin "2") (pinfunction "GND_2") (pintype "passive"))
      (node (ref "U6") (pin "4") (pinfunction "GND_4") (pintype "power_in"))
      (node (ref "U6") (pin "7") (pinfunction "REF1_7") (pintype "input"))
      (node (ref "U7") (pin "2") (pinfunction "GND_2") (pintype "passive"))
      (node (ref "U8") (pin "10") (pinfunction "PGND3_10") (pintype "power_in"))
      (node (ref "U8") (pin "12") (pinfunction "COMPP_12") (pintype "input"))
      (node (ref "U8") (pin "13") (pinfunction "COMPN_13") (pintype "input"))
      (node (ref "U8") (pin "14") (pinfunction "GND_14") (pintype "power_in"))
      (node (ref "U8") (pin "20") (pinfunction "GND_20") (pintype "power_in"))
      (node (ref "U8") (pin "28") (pinfunction "GND_28") (pintype "power_in"))
      (node (ref "U8") (pin "29") (pinfunction "Thermal_pad_29") (pintype "power_in"))
      (node (ref "U8") (pin "6") (pinfunction "PGND1_6") (pintype "power_in"))
      (node (ref "U8") (pin "7") (pinfunction "PGND2_7") (pintype "power_in"))
      (node (ref "Y1") (pin "2") (pinfunction "GND_2") (pintype "power_in"))
    )
    (net (code "51") (name "Net-(D1-C)") (class "Default")
      (node (ref "D1") (pin "1") (pinfunction "C_1") (pintype "passive"))
      (node (ref "R4") (pin "1") (pinfunction "1_1") (pintype "passive"))
    )
    (net (code "52") (name "Net-(D5-C)") (class "Default")
      (node (ref "C18") (pin "1") (pinfunction "1_1") (pintype "passive"))
      (node (ref "C19") (pin "1") (pinfunction "1_1") (pintype "passive"))
      (node (ref "D5") (pin "1") (pinfunction "C_1") (pintype "passive"))
      (node (ref "L1") (pin "1") (pinfunction "1_1") (pintype "passive"))
      (node (ref "U5") (pin "6") (pinfunction "SW_6") (pintype "passive"))
    )
    (net (code "53") (name "Net-(D6-C)") (class "Default")
      (node (ref "C23") (pin "2") (pinfunction "2_2") (pintype "passive"))
      (node (ref "D6") (pin "1") (pinfunction "C_1") (pintype "passive"))
      (node (ref "R20") (pin "1") (pinfunction "1_1") (pintype "passive"))
      (node (ref "U5") (pin "5") (pinfunction "IN_5") (pintype "passive"))
    )
    (net (code "54") (name "Net-(J1-CC1)") (class "Default")
      (node (ref "J1") (pin "A5") (pinfunction "CC1_A5") (pintype "bidirectional"))
      (node (ref "R25") (pin "1") (pinfunction "1_1") (pintype "passive"))
    )
    (net (code "55") (name "Net-(J1-CC2)") (class "Default")
      (node (ref "J1") (pin "B5") (pinfunction "CC2_B5") (pintype "bidirectional"))
      (node (ref "R26") (pin "2") (pinfunction "2_2") (pintype "passive"))
    )
    (net (code "56") (name "Net-(U1A-PD0-OSC_IN)") (class "Default")
      (node (ref "U1") (pin "5") (pinfunction "PD0-OSC_IN_5") (pintype "bidirectional"))
      (node (ref "Y1") (pin "3") (pinfunction "Output_3") (pintype "output"))
    )
    (net (code "57") (name "Net-(U1A-PD1)") (class "Default")
      (node (ref "U1") (pin "6") (pinfunction "PD1_6") (pintype "bidirectional"))
      (node (ref "Y1") (pin "1") (pinfunction "Input_1") (pintype "input"))
    )
    (net (code "58") (name "Net-(U2-CBYP)") (class "Default")
      (node (ref "C7") (pin "2") (pinfunction "2_2") (pintype "passive"))
      (node (ref "U2") (pin "4") (pinfunction "CBYP_4") (pintype "passive"))
    )
    (net (code "59") (name "Net-(U5-BS)") (class "Default")
      (node (ref "C18") (pin "2") (pinfunction "2_2") (pintype "passive"))
      (node (ref "C19") (pin "2") (pinfunction "2_2") (pintype "passive"))
      (node (ref "U5") (pin "1") (pinfunction "BS_1") (pintype "passive"))
    )
    (net (code "60") (name "Net-(U5-EN)") (class "Default")
      (node (ref "R20") (pin "2") (pinfunction "2_2") (pintype "passive"))
      (node (ref "U5") (pin "4") (pinfunction "EN_4") (pintype "passive"))
    )
    (net (code "61") (name "Net-(U5-FB)") (class "Default")
      (node (ref "C17") (pin "1") (pinfunction "1_1") (pintype "passive"))
      (node (ref "R16") (pin "1") (pinfunction "1_1") (pintype "passive"))
      (node (ref "R17") (pin "2") (pinfunction "2_2") (pintype "passive"))
      (node (ref "U5") (pin "3") (pinfunction "FB_3") (pintype "passive"))
    )
    (net (code "62") (name "Net-(U8-CPH)") (class "Default")
      (node (ref "C29") (pin "2") (pinfunction "2_2") (pintype "passive"))
      (node (ref "U8") (pin "2") (pinfunction "CPH_2") (pintype "power_in"))
    )
    (net (code "63") (name "Net-(U8-CPL)") (class "Default")
      (node (ref "C29") (pin "1") (pinfunction "1_1") (pintype "passive"))
      (node (ref "U8") (pin "1") (pinfunction "CPL_1") (pintype "power_in"))
    )
    (net (code "64") (name "Net-(U8-VCP)") (class "Default")
      (node (ref "C28") (pin "1") (pinfunction "1_1") (pintype "passive"))
      (node (ref "U8") (pin "3") (pinfunction "VCP_3") (pintype "power_in"))
    )
    (net (code "65") (name "VBUS") (class "Default")
      (node (ref "D4") (pin "2") (pinfunction "A_2") (pintype "passive"))
      (node (ref "J1") (pin "A4") (pinfunction "VBUS_A_A4") (pintype "power_in"))
      (node (ref "J1") (pin "A9") (pinfunction "VBUS_A_A9") (pintype "power_in"))
      (node (ref "J1") (pin "B4") (pinfunction "VBUS_B_B4") (pintype "power_in"))
      (node (ref "J1") (pin "B9") (pinfunction "VBUS_B_B9") (pintype "power_in"))
    )
    (net (code "66") (name "VCC") (class "Default")
      (node (ref "C11") (pin "2") (pinfunction "2_2") (pintype "passive"))
      (node (ref "C12") (pin "2") (pinfunction "2_2") (pintype "passive"))
      (node (ref "C13") (pin "2") (pinfunction "2_2") (pintype "passive"))
      (node (ref "C14") (pin "2") (pinfunction "2_2") (pintype "passive"))
      (node (ref "C15") (pin "2") (pinfunction "2_2") (pintype "passive"))
      (node (ref "C28") (pin "2") (pinfunction "2_2") (pintype "passive"))
      (node (ref "D2") (pin "2") (pinfunction "K_2") (pintype "passive"))
      (node (ref "D3") (pin "2") (pinfunction "2_2") (pintype "passive"))
      (node (ref "D6") (pin "2") (pinfunction "A_2") (pintype "passive"))
      (node (ref "U8") (pin "11") (pinfunction "VM_11") (pintype "power_in"))
      (node (ref "U8") (pin "4") (pinfunction "VM_4") (pintype "power_in"))
    )
    (net (code "67") (name "VCC_IN") (class "Default")
      (node (ref "D2") (pin "1") (pinfunction "A_1") (pintype "passive"))
      (node (ref "J3") (pin "1") (pinfunction "1_1") (pintype "passive"))
    )
    (net (code "68") (name "unconnected-(J1-SBU1-PadA8)") (class "Default")
      (node (ref "J1") (pin "A8") (pinfunction "SBU1_A8") (pintype "bidirectional+no_connect"))
    )
    (net (code "69") (name "unconnected-(J1-SBU2-PadB8)") (class "Default")
      (node (ref "J1") (pin "B8") (pinfunction "SBU2_B8") (pintype "bidirectional+no_connect"))
    )
    (net (code "70") (name "unconnected-(U1A-PB2-Pad20)") (class "Default")
      (node (ref "U1") (pin "20") (pinfunction "PB2_20") (pintype "bidirectional+no_connect"))
    )
    (net (code "71") (name "unconnected-(U3-PWM-Pad14)") (class "Default")
      (node (ref "U3") (pin "14") (pinfunction "PWM_14") (pintype "output+no_connect"))
    )
    (net (code "72") (name "unconnected-(U3-TEST-Pad6)") (class "Default")
      (node (ref "U3") (pin "6") (pinfunction "TEST_6") (pintype "input+no_connect"))
    )
    (net (code "73") (name "unconnected-(U3-TEST-Pad7)") (class "Default")
      (node (ref "U3") (pin "7") (pinfunction "TEST_7") (pintype "input+no_connect"))
    )
    (net (code "74") (name "unconnected-(U3-TEST-Pad8)") (class "Default")
      (node (ref "U3") (pin "8") (pinfunction "TEST_8") (pintype "input+no_connect"))
    )
    (net (code "75") (name "unconnected-(U3-TEST-Pad9)") (class "Default")
      (node (ref "U3") (pin "9") (pinfunction "TEST_9") (pintype "input+no_connect"))
    )
    (net (code "76") (name "unconnected-(U3-TEST-Pad10)") (class "Default")
      (node (ref "U3") (pin "10") (pinfunction "TEST_10") (pintype "input+no_connect"))
    )
    (net (code "77") (name "unconnected-(U7-NC-Pad5)") (class "Default")
      (node (ref "U7") (pin "5") (pinfunction "NC_5") (pintype "passive+no_connect"))
    )
    (net (code "78") (name "unconnected-(U7-NC-Pad8)") (class "Default")
      (node (ref "U7") (pin "8") (pinfunction "NC_8") (pintype "passive+no_connect"))
    )
    (net (code "79") (name "unconnected-(U8-NC-Pad21)") (class "Default")
      (node (ref "U8") (pin "21") (pinfunction "NC_21") (pintype "passive+no_connect"))
    )
    (net (code "80") (name "unconnected-(U8-~{COMPO}-Pad19)") (class "Default")
      (node (ref "U8") (pin "19") (pinfunction "~{COMPO}_19") (pintype "open_collector+no_connect"))
    )
  )
)
